# christmas_tree_second.net
KiCad netlist of a schematic drawn in Altium Designer
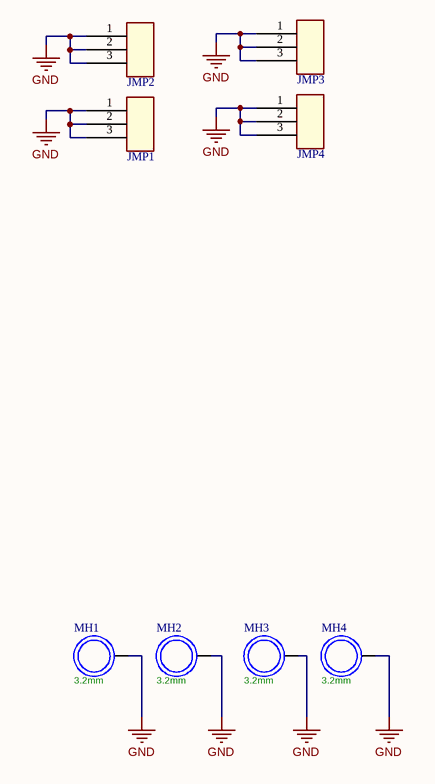
[diagram p0: christmas_tree_second.SchDoc]

(export (version "E")
  (design (tool "Eeschema 10.0.6"))
  (components
    (comp (ref "JMP1")
      (value "JUMPER")
      (footprint "CON-HDR_3X1X254")
      (libsource (lib "Diamond") (part "CON-HDR_3X1X254"))
    )
    (comp (ref "JMP2")
      (value "JUMPER")
      (footprint "CON-HDR_3X1X254")
      (libsource (lib "Diamond") (part "CON-HDR_3X1X254"))
    )
    (comp (ref "JMP3")
      (value "JUMPER")
      (footprint "CON-HDR_3X1X254")
      (libsource (lib "Diamond") (part "CON-HDR_3X1X254"))
    )
    (comp (ref "JMP4")
      (value "JUMPER")
      (footprint "CON-HDR_3X1X254")
      (libsource (lib "Diamond") (part "CON-HDR_3X1X254"))
    )
    (comp (ref "MH1")
      (value "MOUNT-PAD-ROUND_3.2")
      (footprint "HOLE-3-2MM")
      (description "MOUNT-PAD-ROUND3.2")
      (fields
        (field (name "HOLE_DIAMETER") "3.2mm")
        (field (name "APPROVED") "NO")
        (field (name "CHECKED BY") "*")
      )
      (libsource (lib "Firmwave_Mounting") (part "MISC-MH_3.2"))
    )
    (comp (ref "MH2")
      (value "MOUNT-PAD-ROUND_3.2")
      (footprint "HOLE-3-2MM")
      (description "MOUNT-PAD-ROUND3.2")
      (fields
        (field (name "HOLE_DIAMETER") "3.2mm")
        (field (name "APPROVED") "NO")
        (field (name "CHECKED BY") "*")
      )
      (libsource (lib "Firmwave_Mounting") (part "MISC-MH_3.2"))
    )
    (comp (ref "MH3")
      (value "MOUNT-PAD-ROUND_3.2")
      (footprint "HOLE-3-2MM")
      (description "MOUNT-PAD-ROUND3.2")
      (fields
        (field (name "HOLE_DIAMETER") "3.2mm")
        (field (name "APPROVED") "NO")
        (field (name "CHECKED BY") "*")
      )
      (libsource (lib "Firmwave_Mounting") (part "MISC-MH_3.2"))
    )
    (comp (ref "MH4")
      (value "MOUNT-PAD-ROUND_3.2")
      (footprint "HOLE-3-2MM")
      (description "MOUNT-PAD-ROUND3.2")
      (fields
        (field (name "HOLE_DIAMETER") "3.2mm")
        (field (name "APPROVED") "NO")
        (field (name "CHECKED BY") "*")
      )
      (libsource (lib "Firmwave_Mounting") (part "MISC-MH_3.2"))
    )
  )
  (nets
    (net (code "1") (name "GND") (class "Default")
      (node (ref "JMP1") (pin "1") (pinfunction "1_1") (pintype "passive"))
      (node (ref "JMP1") (pin "2") (pinfunction "2_2") (pintype "passive"))
      (node (ref "JMP1") (pin "3") (pinfunction "3_3") (pintype "passive"))
      (node (ref "JMP2") (pin "1") (pinfunction "1_1") (pintype "passive"))
      (node (ref "JMP2") (pin "2") (pinfunction "2_2") (pintype "passive"))
      (node (ref "JMP2") (pin "3") (pinfunction "3_3") (pintype "passive"))
      (node (ref "JMP3") (pin "1") (pinfunction "1_1") (pintype "passive"))
      (node (ref "JMP3") (pin "2") (pinfunction "2_2") (pintype "passive"))
      (node (ref "JMP3") (pin "3") (pinfunction "3_3") (pintype "passive"))
      (node (ref "JMP4") (pin "1") (pinfunction "1_1") (pintype "passive"))
      (node (ref "JMP4") (pin "2") (pinfunction "2_2") (pintype "passive"))
      (node (ref "JMP4") (pin "3") (pinfunction "3_3") (pintype "passive"))
      (node (ref "MH1") (pin "1") (pinfunction "1_1") (pintype "passive"))
      (node (ref "MH2") (pin "1") (pinfunction "1_1") (pintype "passive"))
      (node (ref "MH3") (pin "1") (pinfunction "1_1") (pintype "passive"))
      (node (ref "MH4") (pin "1") (pinfunction "1_1") (pintype "passive"))
    )
  )
)
